# Handle.net
KiCad netlist of a schematic drawn in Altium Designer
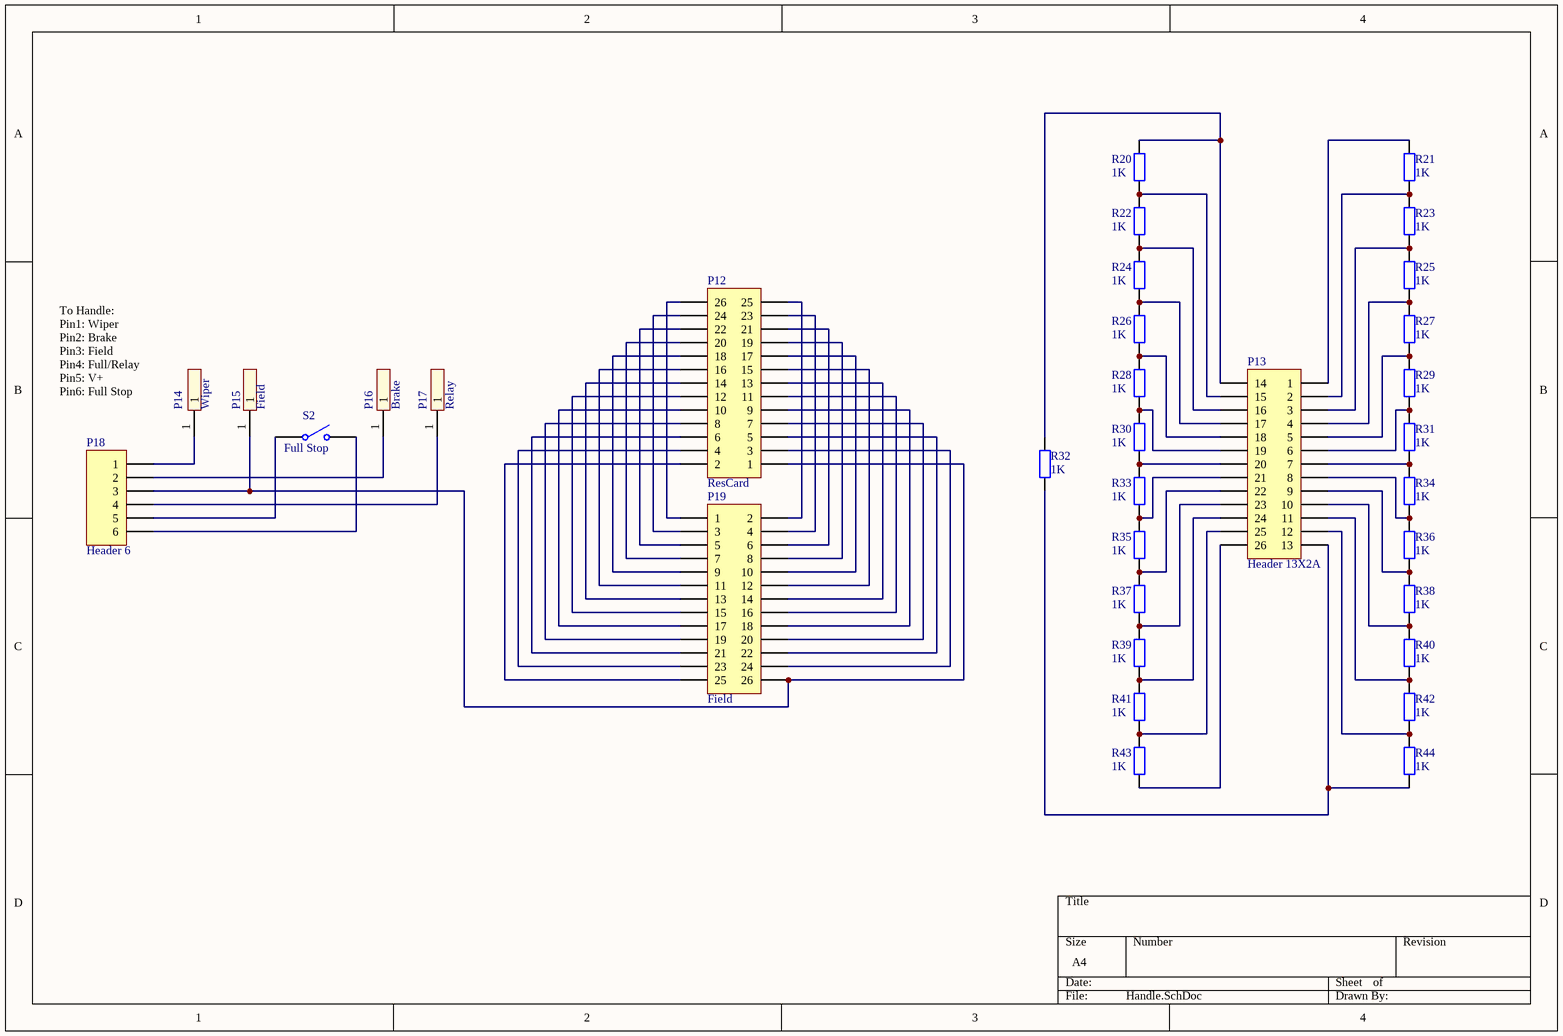
[diagram p0: Handle.SchDoc]

(export (version "E")
  (design (tool "Eeschema 10.0.6"))
  (components
    (comp (ref "P12")
      (value "ResCard")
      (footprint "HDR2X13")
      (description "Header, 13-Pin, Dual row")
      (fields (field (name "PUBLISHER") "Altium Limited"))
      (libsource (lib "Miscellaneous Connectors") (part "Header 13X2"))
    )
    (comp (ref "P13")
      (value "Header 13X2A")
      (footprint "HDR2X13")
      (description "Header, 13-Pin, Dual row")
      (fields (field (name "PUBLISHER") "Altium Limited"))
      (libsource (lib "Miscellaneous Connectors") (part "Header 13X2A"))
    )
    (comp (ref "P14") (value "Wiper") (footprint "1Pin") (libsource (lib "Schlib1") (part "Component_1")))
    (comp (ref "P15") (value "Field") (footprint "1Pin") (libsource (lib "SpecificComponents") (part "1Pin")))
    (comp (ref "P16") (value "Brake") (footprint "1Pin") (libsource (lib "Schlib1") (part "Component_1")))
    (comp (ref "P17") (value "Relay") (footprint "1Pin") (libsource (lib "Schlib1") (part "Component_1")))
    (comp (ref "P18")
      (value "Header 6")
      (footprint "Interconnect")
      (description "Header, 6-Pin")
      (fields (field (name "PUBLISHER") "Altium Limited"))
      (libsource (lib "Miscellaneous Connectors") (part "Header 6"))
    )
    (comp (ref "P19")
      (value "Field")
      (footprint "Wiper Field")
      (description "Header, 13-Pin, Dual row")
      (fields (field (name "PUBLISHER") "Altium Limited"))
      (libsource (lib "") (part "Header 13X2_1"))
    )
    (comp (ref "R20")
      (value "1K")
      (footprint "Res Linear")
      (description "Resistor")
      (fields (field (name "Comment") "Res2") (field (name "PUBLISHER") "Altium Limited"))
      (libsource (lib "Miscellaneous Devices") (part "Res2"))
    )
    (comp (ref "R21")
      (value "1K")
      (footprint "Res Linear")
      (description "Resistor")
      (fields (field (name "Comment") "Res2") (field (name "PUBLISHER") "Altium Limited"))
      (libsource (lib "Miscellaneous Devices") (part "Res2"))
    )
    (comp (ref "R22")
      (value "1K")
      (footprint "Res Linear")
      (description "Resistor")
      (fields (field (name "Comment") "Res2") (field (name "PUBLISHER") "Altium Limited"))
      (libsource (lib "Miscellaneous Devices") (part "Res2"))
    )
    (comp (ref "R23")
      (value "1K")
      (footprint "Res Linear")
      (description "Resistor")
      (fields (field (name "Comment") "Res2") (field (name "PUBLISHER") "Altium Limited"))
      (libsource (lib "Miscellaneous Devices") (part "Res2"))
    )
    (comp (ref "R24")
      (value "1K")
      (footprint "Res Linear")
      (description "Resistor")
      (fields (field (name "Comment") "Res2") (field (name "PUBLISHER") "Altium Limited"))
      (libsource (lib "Miscellaneous Devices") (part "Res2"))
    )
    (comp (ref "R25")
      (value "1K")
      (footprint "Res Linear")
      (description "Resistor")
      (fields (field (name "Comment") "Res2") (field (name "PUBLISHER") "Altium Limited"))
      (libsource (lib "Miscellaneous Devices") (part "Res2"))
    )
    (comp (ref "R26")
      (value "1K")
      (footprint "Res Linear")
      (description "Resistor")
      (fields (field (name "Comment") "Res2") (field (name "PUBLISHER") "Altium Limited"))
      (libsource (lib "Miscellaneous Devices") (part "Res2"))
    )
    (comp (ref "R27")
      (value "1K")
      (footprint "Res Linear")
      (description "Resistor")
      (fields (field (name "Comment") "Res2") (field (name "PUBLISHER") "Altium Limited"))
      (libsource (lib "Miscellaneous Devices") (part "Res2"))
    )
    (comp (ref "R28")
      (value "1K")
      (footprint "Res Linear")
      (description "Resistor")
      (fields (field (name "Comment") "Res2") (field (name "PUBLISHER") "Altium Limited"))
      (libsource (lib "Miscellaneous Devices") (part "Res2"))
    )
    (comp (ref "R29")
      (value "1K")
      (footprint "Res Linear")
      (description "Resistor")
      (fields (field (name "Comment") "Res2") (field (name "PUBLISHER") "Altium Limited"))
      (libsource (lib "Miscellaneous Devices") (part "Res2"))
    )
    (comp (ref "R30")
      (value "1K")
      (footprint "Res Linear")
      (description "Resistor")
      (fields (field (name "Comment") "Res2") (field (name "PUBLISHER") "Altium Limited"))
      (libsource (lib "Miscellaneous Devices") (part "Res2"))
    )
    (comp (ref "R31")
      (value "1K")
      (footprint "Res Linear")
      (description "Resistor")
      (fields (field (name "Comment") "Res2") (field (name "PUBLISHER") "Altium Limited"))
      (libsource (lib "Miscellaneous Devices") (part "Res2"))
    )
    (comp (ref "R32")
      (value "1K")
      (footprint "Res Linear")
      (description "Resistor")
      (fields (field (name "Comment") "Res2") (field (name "PUBLISHER") "Altium Limited"))
      (libsource (lib "") (part "Res2_1"))
    )
    (comp (ref "R33")
      (value "1K")
      (footprint "Res Linear")
      (description "Resistor")
      (fields (field (name "Comment") "Res2") (field (name "PUBLISHER") "Altium Limited"))
      (libsource (lib "Miscellaneous Devices") (part "Res2"))
    )
    (comp (ref "R34")
      (value "1K")
      (footprint "Res Linear")
      (description "Resistor")
      (fields (field (name "Comment") "Res2") (field (name "PUBLISHER") "Altium Limited"))
      (libsource (lib "Miscellaneous Devices") (part "Res2"))
    )
    (comp (ref "R35")
      (value "1K")
      (footprint "Res Linear")
      (description "Resistor")
      (fields (field (name "Comment") "Res2") (field (name "PUBLISHER") "Altium Limited"))
      (libsource (lib "Miscellaneous Devices") (part "Res2"))
    )
    (comp (ref "R36")
      (value "1K")
      (footprint "Res Linear")
      (description "Resistor")
      (fields (field (name "Comment") "Res2") (field (name "PUBLISHER") "Altium Limited"))
      (libsource (lib "Miscellaneous Devices") (part "Res2"))
    )
    (comp (ref "R37")
      (value "1K")
      (footprint "Res Linear")
      (description "Resistor")
      (fields (field (name "Comment") "Res2") (field (name "PUBLISHER") "Altium Limited"))
      (libsource (lib "Miscellaneous Devices") (part "Res2"))
    )
    (comp (ref "R38")
      (value "1K")
      (footprint "Res Linear")
      (description "Resistor")
      (fields (field (name "Comment") "Res2") (field (name "PUBLISHER") "Altium Limited"))
      (libsource (lib "Miscellaneous Devices") (part "Res2"))
    )
    (comp (ref "R39")
      (value "1K")
      (footprint "Res Linear")
      (description "Resistor")
      (fields (field (name "Comment") "Res2") (field (name "PUBLISHER") "Altium Limited"))
      (libsource (lib "Miscellaneous Devices") (part "Res2"))
    )
    (comp (ref "R40")
      (value "1K")
      (footprint "Res Linear")
      (description "Resistor")
      (fields (field (name "Comment") "Res2") (field (name "PUBLISHER") "Altium Limited"))
      (libsource (lib "Miscellaneous Devices") (part "Res2"))
    )
    (comp (ref "R41")
      (value "1K")
      (footprint "Res Linear")
      (description "Resistor")
      (fields (field (name "Comment") "Res2") (field (name "PUBLISHER") "Altium Limited"))
      (libsource (lib "Miscellaneous Devices") (part "Res2"))
    )
    (comp (ref "R42")
      (value "1K")
      (footprint "Res Linear")
      (description "Resistor")
      (fields (field (name "Comment") "Res2") (field (name "PUBLISHER") "Altium Limited"))
      (libsource (lib "Miscellaneous Devices") (part "Res2"))
    )
    (comp (ref "R43")
      (value "1K")
      (footprint "Res Linear")
      (description "Resistor")
      (fields (field (name "Comment") "Res2") (field (name "PUBLISHER") "Altium Limited"))
      (libsource (lib "Miscellaneous Devices") (part "Res2"))
    )
    (comp (ref "R44")
      (value "1K")
      (footprint "Res Linear")
      (description "Resistor")
      (fields (field (name "Comment") "Res2") (field (name "PUBLISHER") "Altium Limited"))
      (libsource (lib "Miscellaneous Devices") (part "Res2"))
    )
    (comp (ref "S2")
      (value "Full Stop")
      (footprint "HDR1X2")
      (description "Single-Pole, Single-Throw Switch")
      (fields (field (name "PUBLISHER") "Altium Limited"))
      (libsource (lib "Miscellaneous Devices") (part "SW-SPST"))
    )
  )
  (nets
    (net (code "1") (name "Net-(P12-Pad1)") (class "Default")
      (node (ref "P12") (pin "1") (pinfunction "1_1") (pintype "passive"))
      (node (ref "P15") (pin "1") (pinfunction "1_1") (pintype "passive"))
      (node (ref "P18") (pin "3") (pinfunction "3_3") (pintype "passive"))
      (node (ref "P19") (pin "26") (pinfunction "26_26") (pintype "passive"))
    )
    (net (code "2") (name "Net-(P12-Pad2)") (class "Default")
      (node (ref "P12") (pin "2") (pinfunction "2_2") (pintype "passive"))
      (node (ref "P19") (pin "25") (pinfunction "25_25") (pintype "passive"))
    )
    (net (code "3") (name "Net-(P12-Pad3)") (class "Default")
      (node (ref "P12") (pin "3") (pinfunction "3_3") (pintype "passive"))
      (node (ref "P19") (pin "24") (pinfunction "24_24") (pintype "passive"))
    )
    (net (code "4") (name "Net-(P12-Pad4)") (class "Default")
      (node (ref "P12") (pin "4") (pinfunction "4_4") (pintype "passive"))
      (node (ref "P19") (pin "23") (pinfunction "23_23") (pintype "passive"))
    )
    (net (code "5") (name "Net-(P12-Pad5)") (class "Default")
      (node (ref "P12") (pin "5") (pinfunction "5_5") (pintype "passive"))
      (node (ref "P19") (pin "22") (pinfunction "22_22") (pintype "passive"))
    )
    (net (code "6") (name "Net-(P12-Pad6)") (class "Default")
      (node (ref "P12") (pin "6") (pinfunction "6_6") (pintype "passive"))
      (node (ref "P19") (pin "21") (pinfunction "21_21") (pintype "passive"))
    )
    (net (code "7") (name "Net-(P12-Pad7)") (class "Default")
      (node (ref "P12") (pin "7") (pinfunction "7_7") (pintype "passive"))
      (node (ref "P19") (pin "20") (pinfunction "20_20") (pintype "passive"))
    )
    (net (code "8") (name "Net-(P12-Pad8)") (class "Default")
      (node (ref "P12") (pin "8") (pinfunction "8_8") (pintype "passive"))
      (node (ref "P19") (pin "19") (pinfunction "19_19") (pintype "passive"))
    )
    (net (code "9") (name "Net-(P12-Pad9)") (class "Default")
      (node (ref "P12") (pin "9") (pinfunction "9_9") (pintype "passive"))
      (node (ref "P19") (pin "18") (pinfunction "18_18") (pintype "passive"))
    )
    (net (code "10") (name "Net-(P12-Pad10)") (class "Default")
      (node (ref "P12") (pin "10") (pinfunction "10_10") (pintype "passive"))
      (node (ref "P19") (pin "17") (pinfunction "17_17") (pintype "passive"))
    )
    (net (code "11") (name "Net-(P12-Pad11)") (class "Default")
      (node (ref "P12") (pin "11") (pinfunction "11_11") (pintype "passive"))
      (node (ref "P19") (pin "16") (pinfunction "16_16") (pintype "passive"))
    )
    (net (code "12") (name "Net-(P12-Pad12)") (class "Default")
      (node (ref "P12") (pin "12") (pinfunction "12_12") (pintype "passive"))
      (node (ref "P19") (pin "15") (pinfunction "15_15") (pintype "passive"))
    )
    (net (code "13") (name "Net-(P12-Pad13)") (class "Default")
      (node (ref "P12") (pin "13") (pinfunction "13_13") (pintype "passive"))
      (node (ref "P19") (pin "14") (pinfunction "14_14") (pintype "passive"))
    )
    (net (code "14") (name "Net-(P12-Pad14)") (class "Default")
      (node (ref "P12") (pin "14") (pinfunction "14_14") (pintype "passive"))
      (node (ref "P19") (pin "13") (pinfunction "13_13") (pintype "passive"))
    )
    (net (code "15") (name "Net-(P12-Pad15)") (class "Default")
      (node (ref "P12") (pin "15") (pinfunction "15_15") (pintype "passive"))
      (node (ref "P19") (pin "12") (pinfunction "12_12") (pintype "passive"))
    )
    (net (code "16") (name "Net-(P12-Pad16)") (class "Default")
      (node (ref "P12") (pin "16") (pinfunction "16_16") (pintype "passive"))
      (node (ref "P19") (pin "11") (pinfunction "11_11") (pintype "passive"))
    )
    (net (code "17") (name "Net-(P12-Pad17)") (class "Default")
      (node (ref "P12") (pin "17") (pinfunction "17_17") (pintype "passive"))
      (node (ref "P19") (pin "10") (pinfunction "10_10") (pintype "passive"))
    )
    (net (code "18") (name "Net-(P12-Pad18)") (class "Default")
      (node (ref "P12") (pin "18") (pinfunction "18_18") (pintype "passive"))
      (node (ref "P19") (pin "9") (pinfunction "9_9") (pintype "passive"))
    )
    (net (code "19") (name "Net-(P12-Pad19)") (class "Default")
      (node (ref "P12") (pin "19") (pinfunction "19_19") (pintype "passive"))
      (node (ref "P19") (pin "8") (pinfunction "8_8") (pintype "passive"))
    )
    (net (code "20") (name "Net-(P12-Pad20)") (class "Default")
      (node (ref "P12") (pin "20") (pinfunction "20_20") (pintype "passive"))
      (node (ref "P19") (pin "7") (pinfunction "7_7") (pintype "passive"))
    )
    (net (code "21") (name "Net-(P12-Pad21)") (class "Default")
      (node (ref "P12") (pin "21") (pinfunction "21_21") (pintype "passive"))
      (node (ref "P19") (pin "6") (pinfunction "6_6") (pintype "passive"))
    )
    (net (code "22") (name "Net-(P12-Pad22)") (class "Default")
      (node (ref "P12") (pin "22") (pinfunction "22_22") (pintype "passive"))
      (node (ref "P19") (pin "5") (pinfunction "5_5") (pintype "passive"))
    )
    (net (code "23") (name "Net-(P12-Pad23)") (class "Default")
      (node (ref "P12") (pin "23") (pinfunction "23_23") (pintype "passive"))
      (node (ref "P19") (pin "4") (pinfunction "4_4") (pintype "passive"))
    )
    (net (code "24") (name "Net-(P12-Pad24)") (class "Default")
      (node (ref "P12") (pin "24") (pinfunction "24_24") (pintype "passive"))
      (node (ref "P19") (pin "3") (pinfunction "3_3") (pintype "passive"))
    )
    (net (code "25") (name "Net-(P12-Pad25)") (class "Default")
      (node (ref "P12") (pin "25") (pinfunction "25_25") (pintype "passive"))
      (node (ref "P19") (pin "2") (pinfunction "2_2") (pintype "passive"))
    )
    (net (code "26") (name "Net-(P12-Pad26)") (class "Default")
      (node (ref "P12") (pin "26") (pinfunction "26_26") (pintype "passive"))
      (node (ref "P19") (pin "1") (pinfunction "1_1") (pintype "passive"))
    )
    (net (code "27") (name "Net-(P13-Pad1)") (class "Default")
      (node (ref "P13") (pin "1") (pinfunction "1_1") (pintype "passive"))
      (node (ref "R21") (pin "1") (pinfunction "1_1") (pintype "passive"))
    )
    (net (code "28") (name "Net-(P13-Pad2)") (class "Default")
      (node (ref "P13") (pin "2") (pinfunction "2_2") (pintype "passive"))
      (node (ref "R21") (pin "2") (pinfunction "2_2") (pintype "passive"))
      (node (ref "R23") (pin "1") (pinfunction "1_1") (pintype "passive"))
    )
    (net (code "29") (name "Net-(P13-Pad3)") (class "Default")
      (node (ref "P13") (pin "3") (pinfunction "3_3") (pintype "passive"))
      (node (ref "R23") (pin "2") (pinfunction "2_2") (pintype "passive"))
      (node (ref "R25") (pin "1") (pinfunction "1_1") (pintype "passive"))
    )
    (net (code "30") (name "Net-(P13-Pad4)") (class "Default")
      (node (ref "P13") (pin "4") (pinfunction "4_4") (pintype "passive"))
      (node (ref "R25") (pin "2") (pinfunction "2_2") (pintype "passive"))
      (node (ref "R27") (pin "1") (pinfunction "1_1") (pintype "passive"))
    )
    (net (code "31") (name "Net-(P13-Pad5)") (class "Default")
      (node (ref "P13") (pin "5") (pinfunction "5_5") (pintype "passive"))
      (node (ref "R27") (pin "2") (pinfunction "2_2") (pintype "passive"))
      (node (ref "R29") (pin "1") (pinfunction "1_1") (pintype "passive"))
    )
    (net (code "32") (name "Net-(P13-Pad6)") (class "Default")
      (node (ref "P13") (pin "6") (pinfunction "6_6") (pintype "passive"))
      (node (ref "R29") (pin "2") (pinfunction "2_2") (pintype "passive"))
      (node (ref "R31") (pin "1") (pinfunction "1_1") (pintype "passive"))
    )
    (net (code "33") (name "Net-(P13-Pad7)") (class "Default")
      (node (ref "P13") (pin "7") (pinfunction "7_7") (pintype "passive"))
      (node (ref "R31") (pin "2") (pinfunction "2_2") (pintype "passive"))
      (node (ref "R34") (pin "1") (pinfunction "1_1") (pintype "passive"))
    )
    (net (code "34") (name "Net-(P13-Pad8)") (class "Default")
      (node (ref "P13") (pin "8") (pinfunction "8_8") (pintype "passive"))
      (node (ref "R34") (pin "2") (pinfunction "2_2") (pintype "passive"))
      (node (ref "R36") (pin "1") (pinfunction "1_1") (pintype "passive"))
    )
    (net (code "35") (name "Net-(P13-Pad9)") (class "Default")
      (node (ref "P13") (pin "9") (pinfunction "9_9") (pintype "passive"))
      (node (ref "R36") (pin "2") (pinfunction "2_2") (pintype "passive"))
      (node (ref "R38") (pin "1") (pinfunction "1_1") (pintype "passive"))
    )
    (net (code "36") (name "Net-(P13-Pad10)") (class "Default")
      (node (ref "P13") (pin "10") (pinfunction "10_10") (pintype "passive"))
      (node (ref "R38") (pin "2") (pinfunction "2_2") (pintype "passive"))
      (node (ref "R40") (pin "1") (pinfunction "1_1") (pintype "passive"))
    )
    (net (code "37") (name "Net-(P13-Pad11)") (class "Default")
      (node (ref "P13") (pin "11") (pinfunction "11_11") (pintype "passive"))
      (node (ref "R40") (pin "2") (pinfunction "2_2") (pintype "passive"))
      (node (ref "R42") (pin "1") (pinfunction "1_1") (pintype "passive"))
    )
    (net (code "38") (name "Net-(P13-Pad12)") (class "Default")
      (node (ref "P13") (pin "12") (pinfunction "12_12") (pintype "passive"))
      (node (ref "R42") (pin "2") (pinfunction "2_2") (pintype "passive"))
      (node (ref "R44") (pin "1") (pinfunction "1_1") (pintype "passive"))
    )
    (net (code "39") (name "Net-(P13-Pad13)") (class "Default")
      (node (ref "P13") (pin "13") (pinfunction "13_13") (pintype "passive"))
      (node (ref "R32") (pin "1") (pinfunction "1_1") (pintype "passive"))
      (node (ref "R44") (pin "2") (pinfunction "2_2") (pintype "passive"))
    )
    (net (code "40") (name "Net-(P13-Pad14)") (class "Default")
      (node (ref "P13") (pin "14") (pinfunction "14_14") (pintype "passive"))
      (node (ref "R20") (pin "1") (pinfunction "1_1") (pintype "passive"))
      (node (ref "R32") (pin "2") (pinfunction "2_2") (pintype "passive"))
    )
    (net (code "41") (name "Net-(P13-Pad15)") (class "Default")
      (node (ref "P13") (pin "15") (pinfunction "15_15") (pintype "passive"))
      (node (ref "R20") (pin "2") (pinfunction "2_2") (pintype "passive"))
      (node (ref "R22") (pin "1") (pinfunction "1_1") (pintype "passive"))
    )
    (net (code "42") (name "Net-(P13-Pad16)") (class "Default")
      (node (ref "P13") (pin "16") (pinfunction "16_16") (pintype "passive"))
      (node (ref "R22") (pin "2") (pinfunction "2_2") (pintype "passive"))
      (node (ref "R24") (pin "1") (pinfunction "1_1") (pintype "passive"))
    )
    (net (code "43") (name "Net-(P13-Pad17)") (class "Default")
      (node (ref "P13") (pin "17") (pinfunction "17_17") (pintype "passive"))
      (node (ref "R24") (pin "2") (pinfunction "2_2") (pintype "passive"))
      (node (ref "R26") (pin "1") (pinfunction "1_1") (pintype "passive"))
    )
    (net (code "44") (name "Net-(P13-Pad18)") (class "Default")
      (node (ref "P13") (pin "18") (pinfunction "18_18") (pintype "passive"))
      (node (ref "R26") (pin "2") (pinfunction "2_2") (pintype "passive"))
      (node (ref "R28") (pin "1") (pinfunction "1_1") (pintype "passive"))
    )
    (net (code "45") (name "Net-(P13-Pad19)") (class "Default")
      (node (ref "P13") (pin "19") (pinfunction "19_19") (pintype "passive"))
      (node (ref "R28") (pin "2") (pinfunction "2_2") (pintype "passive"))
      (node (ref "R30") (pin "1") (pinfunction "1_1") (pintype "passive"))
    )
    (net (code "46") (name "Net-(P13-Pad20)") (class "Default")
      (node (ref "P13") (pin "20") (pinfunction "20_20") (pintype "passive"))
      (node (ref "R30") (pin "2") (pinfunction "2_2") (pintype "passive"))
      (node (ref "R33") (pin "1") (pinfunction "1_1") (pintype "passive"))
    )
    (net (code "47") (name "Net-(P13-Pad21)") (class "Default")
      (node (ref "P13") (pin "21") (pinfunction "21_21") (pintype "passive"))
      (node (ref "R33") (pin "2") (pinfunction "2_2") (pintype "passive"))
      (node (ref "R35") (pin "1") (pinfunction "1_1") (pintype "passive"))
    )
    (net (code "48") (name "Net-(P13-Pad22)") (class "Default")
      (node (ref "P13") (pin "22") (pinfunction "22_22") (pintype "passive"))
      (node (ref "R35") (pin "2") (pinfunction "2_2") (pintype "passive"))
      (node (ref "R37") (pin "1") (pinfunction "1_1") (pintype "passive"))
    )
    (net (code "49") (name "Net-(P13-Pad23)") (class "Default")
      (node (ref "P13") (pin "23") (pinfunction "23_23") (pintype "passive"))
      (node (ref "R37") (pin "2") (pinfunction "2_2") (pintype "passive"))
      (node (ref "R39") (pin "1") (pinfunction "1_1") (pintype "passive"))
    )
    (net (code "50") (name "Net-(P13-Pad24)") (class "Default")
      (node (ref "P13") (pin "24") (pinfunction "24_24") (pintype "passive"))
      (node (ref "R39") (pin "2") (pinfunction "2_2") (pintype "passive"))
      (node (ref "R41") (pin "1") (pinfunction "1_1") (pintype "passive"))
    )
    (net (code "51") (name "Net-(P13-Pad25)") (class "Default")
      (node (ref "P13") (pin "25") (pinfunction "25_25") (pintype "passive"))
      (node (ref "R41") (pin "2") (pinfunction "2_2") (pintype "passive"))
      (node (ref "R43") (pin "1") (pinfunction "1_1") (pintype "passive"))
    )
    (net (code "52") (name "Net-(P13-Pad26)") (class "Default")
      (node (ref "P13") (pin "26") (pinfunction "26_26") (pintype "passive"))
      (node (ref "R43") (pin "2") (pinfunction "2_2") (pintype "passive"))
    )
    (net (code "53") (name "Net-(P14-Pad1)") (class "Default")
      (node (ref "P14") (pin "1") (pinfunction "1_1") (pintype "passive"))
      (node (ref "P18") (pin "1") (pinfunction "1_1") (pintype "passive"))
    )
    (net (code "54") (name "Net-(P16-Pad1)") (class "Default")
      (node (ref "P16") (pin "1") (pinfunction "1_1") (pintype "passive"))
      (node (ref "P18") (pin "2") (pinfunction "2_2") (pintype "passive"))
    )
    (net (code "55") (name "Net-(P17-Pad1)") (class "Default")
      (node (ref "P17") (pin "1") (pinfunction "1_1") (pintype "passive"))
      (node (ref "P18") (pin "4") (pinfunction "4_4") (pintype "passive"))
    )
    (net (code "56") (name "Net-(S2-COMMON)") (class "Default")
      (node (ref "P18") (pin "5") (pinfunction "5_5") (pintype "passive"))
      (node (ref "S2") (pin "1") (pinfunction "COMMON_1") (pintype "passive"))
    )
    (net (code "57") (name "Net-(S2-NO)") (class "Default")
      (node (ref "P18") (pin "6") (pinfunction "6_6") (pintype "passive"))
      (node (ref "S2") (pin "2") (pinfunction "NO_2") (pintype "passive"))
    )
  )
)
